# schematic.net
KiCad netlist of a schematic drawn in Altium Designer
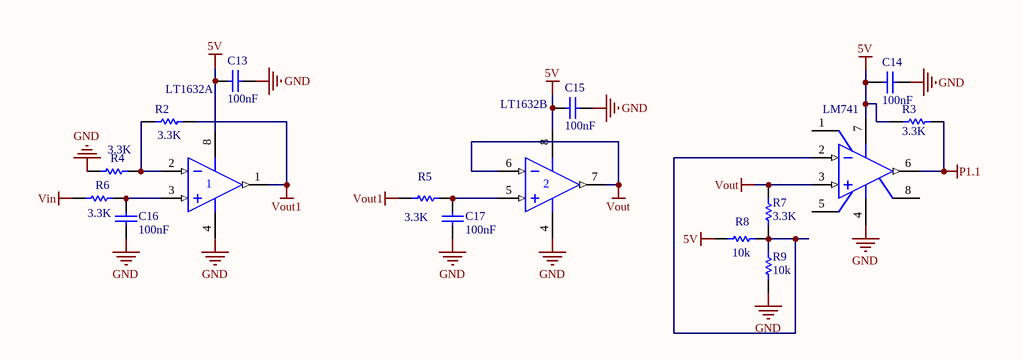
[diagram p0: schematic.SchDoc]

(export (version "E")
  (design (tool "Eeschema 10.0.6"))
  (components
    (comp (ref "C13")
      (value "100nF")
      (footprint "RAD-0.1")
      (description "Capacitor")
      (fields (field (name "Comment") "Cap") (field (name "PUBLISHER") "Altium Limited"))
      (libsource (lib "Miscellaneous Devices") (part "Cap"))
    )
    (comp (ref "C14")
      (value "100nF")
      (footprint "RAD-0.1")
      (description "Capacitor")
      (fields (field (name "Comment") "Cap") (field (name "PUBLISHER") "Altium Limited"))
      (libsource (lib "Miscellaneous Devices") (part "Cap"))
    )
    (comp (ref "C15")
      (value "100nF")
      (footprint "RAD-0.1")
      (description "Capacitor")
      (fields (field (name "Comment") "Cap") (field (name "PUBLISHER") "Altium Limited"))
      (libsource (lib "Miscellaneous Devices") (part "Cap"))
    )
    (comp (ref "C16")
      (value "100nF")
      (footprint "RAD-0.1")
      (description "Capacitor")
      (fields (field (name "Comment") "Cap") (field (name "PUBLISHER") "Altium Limited"))
      (libsource (lib "Miscellaneous Devices") (part "Cap"))
    )
    (comp (ref "C17")
      (value "100nF")
      (footprint "RAD-0.1")
      (description "Capacitor")
      (fields (field (name "Comment") "Cap") (field (name "PUBLISHER") "Altium Limited"))
      (libsource (lib "Miscellaneous Devices") (part "Cap"))
    )
    (comp (ref "LM741")
      (value "LM741CN")
      (footprint "N08E")
      (description "Operational Amplifier, 8-pin MDIP")
      (fields
        (field (name "MANUFACTURER") "National Semiconductor")
        (field (name "PUBLISHER") "Altium Limited")
      )
      (libsource (lib "NSC Amplifier") (part "LM741CN"))
    )
    (comp (ref "LT1632")
      (value "LT1632")
      (footprint "JG008")
      (description "Dual Operational Amplifier")
      (fields (field (name "PUBLISHER") "Altium Limited"))
      (libsource (lib "TI Operational Amplifier") (part "LM158JG"))
    )
    (comp (ref "R2")
      (value "3.3K")
      (footprint "AXIAL-0.3")
      (description "Resistor")
      (fields (field (name "Comment") "Res1") (field (name "PUBLISHER") "Altium Limited"))
      (libsource (lib "Miscellaneous Devices") (part "Res1"))
    )
    (comp (ref "R3")
      (value "3.3K")
      (footprint "AXIAL-0.3")
      (description "Resistor")
      (fields (field (name "Comment") "Res1") (field (name "PUBLISHER") "Altium Limited"))
      (libsource (lib "Miscellaneous Devices") (part "Res1"))
    )
    (comp (ref "R4")
      (value "3.3K")
      (footprint "AXIAL-0.3")
      (description "Resistor")
      (fields (field (name "Comment") "Res1") (field (name "PUBLISHER") "Altium Limited"))
      (libsource (lib "Miscellaneous Devices") (part "Res1"))
    )
    (comp (ref "R5")
      (value "3.3K")
      (footprint "AXIAL-0.3")
      (description "Resistor")
      (fields (field (name "Comment") "Res1") (field (name "PUBLISHER") "Altium Limited"))
      (libsource (lib "Miscellaneous Devices") (part "Res1"))
    )
    (comp (ref "R6")
      (value "3.3K")
      (footprint "AXIAL-0.3")
      (description "Resistor")
      (fields (field (name "Comment") "Res1") (field (name "PUBLISHER") "Altium Limited"))
      (libsource (lib "Miscellaneous Devices") (part "Res1"))
    )
    (comp (ref "R7")
      (value "3.3K")
      (footprint "AXIAL-0.3")
      (description "Resistor")
      (fields (field (name "Comment") "Res1") (field (name "PUBLISHER") "Altium Limited"))
      (libsource (lib "Miscellaneous Devices") (part "Res1"))
    )
    (comp (ref "R8")
      (value "10k")
      (footprint "AXIAL-0.3")
      (description "Resistor")
      (fields (field (name "Comment") "Res1") (field (name "PUBLISHER") "Altium Limited"))
      (libsource (lib "Miscellaneous Devices") (part "Res1"))
    )
    (comp (ref "R9")
      (value "10k")
      (footprint "AXIAL-0.3")
      (description "Resistor")
      (fields (field (name "Comment") "Res1") (field (name "PUBLISHER") "Altium Limited"))
      (libsource (lib "Miscellaneous Devices") (part "Res1"))
    )
  )
  (nets
    (net (code "1") (name "5V") (class "Default")
      (node (ref "C13") (pin "2") (pinfunction "2_2") (pintype "passive"))
      (node (ref "C14") (pin "2") (pinfunction "2_2") (pintype "passive"))
      (node (ref "C15") (pin "2") (pinfunction "2_2") (pintype "passive"))
      (node (ref "LM741") (pin "7") (pinfunction "V+_7") (pintype "power_in"))
      (node (ref "LT1632") (pin "8") (pinfunction "V+_8") (pintype "power_in"))
      (node (ref "R3") (pin "2") (pinfunction "2_2") (pintype "passive"))
      (node (ref "R8") (pin "1") (pinfunction "1_1") (pintype "passive"))
    )
    (net (code "2") (name "GND") (class "Default")
      (node (ref "C13") (pin "1") (pinfunction "1_1") (pintype "passive"))
      (node (ref "C14") (pin "1") (pinfunction "1_1") (pintype "passive"))
      (node (ref "C15") (pin "1") (pinfunction "1_1") (pintype "passive"))
      (node (ref "C16") (pin "2") (pinfunction "2_2") (pintype "passive"))
      (node (ref "C17") (pin "2") (pinfunction "2_2") (pintype "passive"))
      (node (ref "LM741") (pin "4") (pinfunction "V-_4") (pintype "power_in"))
      (node (ref "LT1632") (pin "4") (pinfunction "V-_4") (pintype "power_in"))
      (node (ref "R4") (pin "1") (pinfunction "1_1") (pintype "passive"))
      (node (ref "R9") (pin "1") (pinfunction "1_1") (pintype "passive"))
    )
    (net (code "3") (name "Net-(LM741-IN-)") (class "Default")
      (node (ref "LM741") (pin "2") (pinfunction "IN-_2") (pintype "input"))
      (node (ref "R7") (pin "1") (pinfunction "1_1") (pintype "passive"))
      (node (ref "R8") (pin "2") (pinfunction "2_2") (pintype "passive"))
      (node (ref "R9") (pin "2") (pinfunction "2_2") (pintype "passive"))
    )
    (net (code "4") (name "Net-(LT1632A-IN+)") (class "Default")
      (node (ref "C16") (pin "1") (pinfunction "1_1") (pintype "passive"))
      (node (ref "LT1632") (pin "3") (pinfunction "IN+_3") (pintype "input"))
      (node (ref "R6") (pin "2") (pinfunction "2_2") (pintype "passive"))
    )
    (net (code "5") (name "Net-(LT1632A-IN-)") (class "Default")
      (node (ref "LT1632") (pin "2") (pinfunction "IN-_2") (pintype "input"))
      (node (ref "R2") (pin "1") (pinfunction "1_1") (pintype "passive"))
      (node (ref "R4") (pin "2") (pinfunction "2_2") (pintype "passive"))
    )
    (net (code "6") (name "Net-(LT1632B-IN+)") (class "Default")
      (node (ref "C17") (pin "1") (pinfunction "1_1") (pintype "passive"))
      (node (ref "LT1632") (pin "5") (pinfunction "IN+_5") (pintype "input"))
      (node (ref "R5") (pin "2") (pinfunction "2_2") (pintype "passive"))
    )
    (net (code "7") (name "P1.1") (class "Default")
      (node (ref "LM741") (pin "6") (pinfunction "OUT_6") (pintype "output"))
      (node (ref "R3") (pin "1") (pinfunction "1_1") (pintype "passive"))
    )
    (net (code "8") (name "Vin") (class "Default")
      (node (ref "R6") (pin "1") (pinfunction "1_1") (pintype "passive"))
    )
    (net (code "9") (name "Vout") (class "Default")
      (node (ref "LM741") (pin "3") (pinfunction "IN+_3") (pintype "input"))
      (node (ref "LT1632") (pin "6") (pinfunction "IN-_6") (pintype "input"))
      (node (ref "LT1632") (pin "7") (pinfunction "OUT_7") (pintype "output"))
      (node (ref "R7") (pin "2") (pinfunction "2_2") (pintype "passive"))
    )
    (net (code "10") (name "Vout1") (class "Default")
      (node (ref "LT1632") (pin "1") (pinfunction "OUT_1") (pintype "output"))
      (node (ref "R2") (pin "2") (pinfunction "2_2") (pintype "passive"))
      (node (ref "R5") (pin "1") (pinfunction "1_1") (pintype "passive"))
    )
    (net (code "11") (name "unconnected-(LM741-NC-Pad8)") (class "Default")
      (node (ref "LM741") (pin "8") (pinfunction "NC_8") (pintype "passive"))
    )
    (net (code "12") (name "unconnected-(LM741-OFS_NULL-Pad1)") (class "Default")
      (node (ref "LM741") (pin "1") (pinfunction "OFS_NULL_1") (pintype "passive"))
    )
    (net (code "13") (name "unconnected-(LM741-OFS_NULL-Pad5)") (class "Default")
      (node (ref "LM741") (pin "5") (pinfunction "OFS_NULL_5") (pintype "passive"))
    )
  )
)
